# FanControllerSch.net
KiCad netlist of a schematic drawn in Altium Designer
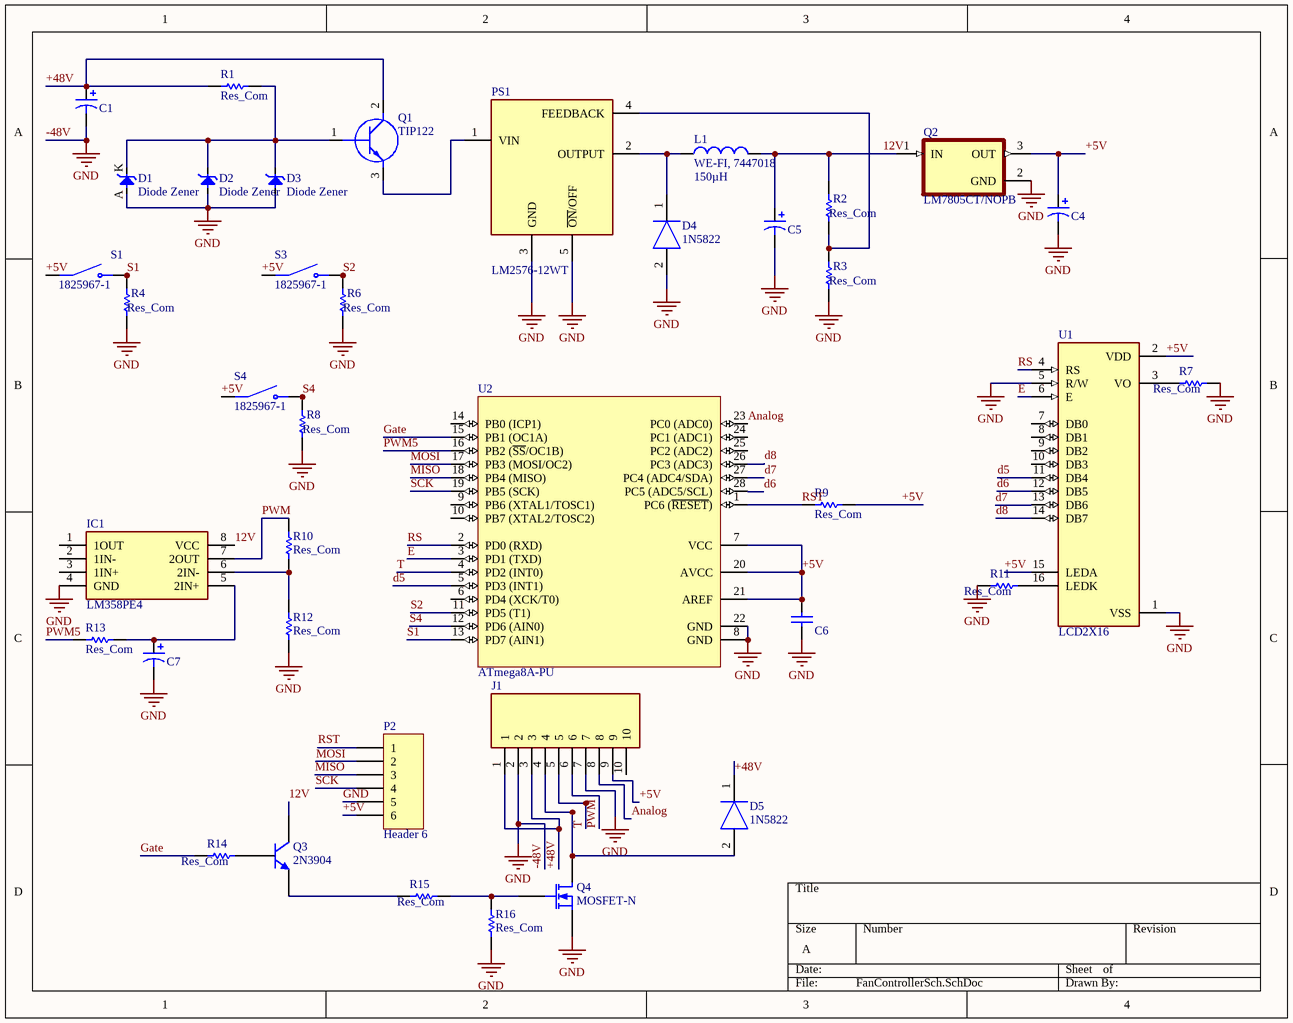
[diagram p0: FanControllerSch.SchDoc]

(export (version "E")
  (design (tool "Eeschema 10.0.6"))
  (components
    (comp (ref "C1")
      (value "100 μF")
      (footprint "Radial 12.5 x 25")
      (description "Electrolitic Capacitor, Thru-Hole")
      (fields
        (field (name "PUBLISHER") "Cynetik Group")
        (field (name "CREATED BY") "Zion Blue")
        (field (name "CONTACT") "cynetik_group@hotmail.com")
      )
      (libsource (lib "Capacitors") (part "Electrolitic Capacitor, Thru-Hole"))
    )
    (comp (ref "C4")
      (value "100 μF")
      (footprint "RADIAL 3.5x7.7")
      (description "Electrolitic Capacitor, Thru-Hole")
      (fields
        (field (name "PUBLISHER") "Cynetik Group")
        (field (name "CREATED BY") "Zion Blue")
        (field (name "CONTACT") "cynetik_group@hotmail.com")
      )
      (libsource (lib "Capacitors") (part "Electrolitic Capacitor, Thru-Hole"))
    )
    (comp (ref "C5")
      (value "100 μF")
      (footprint "RADIAL 3.5x7.7")
      (description "Electrolitic Capacitor, Thru-Hole")
      (fields
        (field (name "PUBLISHER") "Cynetik Group")
        (field (name "CREATED BY") "Zion Blue")
        (field (name "CONTACT") "cynetik_group@hotmail.com")
      )
      (libsource (lib "Capacitors") (part "Electrolitic Capacitor, Thru-Hole"))
    )
    (comp (ref "C6")
      (value "100 nF")
      (footprint "Ceramic Capacitor 2")
      (description "Ceramic Capacitor, Thru-Hole")
      (fields
        (field (name "CREATED BY") "Zion Blue")
        (field (name "PUBLISHER") "Cynetik Group")
        (field (name "CONTACT") "cynetik_group@hotmail.com")
      )
      (libsource (lib "Capacitors") (part "Ceramic Capacitor, Thru-Hole."))
    )
    (comp (ref "C7")
      (value "100 μF")
      (footprint "RADIAL 3.5x7.7")
      (description "Electrolitic Capacitor, Thru-Hole")
      (fields
        (field (name "PUBLISHER") "Cynetik Group")
        (field (name "CREATED BY") "Zion Blue")
        (field (name "CONTACT") "cynetik_group@hotmail.com")
      )
      (libsource (lib "Capacitors") (part "Electrolitic Capacitor, Thru-Hole"))
    )
    (comp (ref "D1")
      (value "Diode Zener")
      (footprint "ONSC-AXIAL_LEAD-2-59-10_P")
      (libsource (lib "") (part "Diode Zener_1"))
    )
    (comp (ref "D2")
      (value "Diode Zener")
      (footprint "ONSC-AXIAL_LEAD-2-59-10_P")
      (libsource (lib "Diodes") (part "Diode Zener"))
    )
    (comp (ref "D3")
      (value "Diode Zener")
      (footprint "ONSC-AXIAL_LEAD-2-59-10_P")
      (libsource (lib "Diodes") (part "Diode Zener"))
    )
    (comp (ref "D4")
      (value "1N5822")
      (footprint "ONSC-AXIAL_LEAD-2-59-10_P")
      (description "Diode")
      (libsource (lib "*") (part "1N5822"))
    )
    (comp (ref "D5")
      (value "1N5822")
      (footprint "ONSC-AXIAL_LEAD-2-59-10_P")
      (description "Diode")
      (libsource (lib "*") (part "1N5822"))
    )
    (comp (ref "IC1")
      (value "LM358PE4")
      (footprint "SamacSys:DIP794W53P254L959H508Q8N")
      (description "Integrated Circuit")
      (fields (field (name "MOUSER PART NUMBER") "595-LM358PE4"))
      (libsource (lib "*") (part "LM358PE4"))
    )
    (comp (ref "J1")
      (value "1-282837-0")
      (footprint "TE_1-282837-0")
      (description "TERMI-BLOK PCB MOUNT 10P")
      (fields (field (name "MF") "TE Connectivity"))
      (libsource (lib "TB-10P-5.08pitch") (part "1-282837-0"))
    )
    (comp (ref "L1")
      (value "WE-FI, 7447018")
      (footprint "TSL0709RA-102KR19-PF")
      (description "WE-FI Leaded Toroidal Line Choke, L = 150µH")
      (fields
        (field (name "PARTNO") "7447018")
        (field (name "MANUFACTURER") "Wurth Elektronik")
        (field (name "ALTIUM_VALUE") "150µH")
        (field (name "CREATED BY") "Baojun Chen")
      )
      (libsource (lib "Inductor") (part "WE-FI, 7447018"))
    )
    (comp (ref "P2")
      (value "Header 6")
      (footprint "HDR1X6")
      (description "Header, 6-Pin")
      (fields (field (name "PUBLISHER") "Altium Limited"))
      (libsource (lib "Miscellaneous Connectors") (part "Header 6"))
    )
    (comp (ref "PS1")
      (value "LM2576-12WT")
      (footprint "SamacSys:TO170P470X1016X1900-5P")
      (description "Power Supply")
      (fields (field (name "MOUSER PART NUMBER") "998-LM2576-12WT"))
      (libsource (lib "*") (part "LM2576-12WT"))
    )
    (comp (ref "Q1")
      (value "TIP122")
      (footprint "SamacSys:TO255P460X1020X2008-3P")
      (description "Transistor BJT NPN")
      (fields (field (name "MOUSER PART NUMBER") "511-TIP122"))
      (libsource (lib "*") (part "TIP122"))
    )
    (comp (ref "Q2")
      (value "LM7805CT/NOPB")
      (footprint "TO254P1054X470X2600-3")
      (description "Linear Voltage Regulator IC 1 Output 1A TO-220-3")
      (fields (field (name "MP") "LM7805CT") (field (name "MF") "ON Semiconductor"))
      (libsource (lib "LDO") (part "LM7805CT/NOPB"))
    )
    (comp (ref "Q3")
      (value "2N3904")
      (footprint "TO-92A")
      (description "NPN General Purpose Amplifier")
      (fields (field (name "PUBLISHER") "Altium Limited"))
      (libsource (lib "Miscellaneous Devices") (part "2N3904"))
    )
    (comp (ref "Q4")
      (value "MOSFET-N")
      (footprint "TO-220AB")
      (description "N-Channel MOSFET")
      (fields (field (name "PUBLISHER") "Altium Limited"))
      (libsource (lib "Miscellaneous Devices") (part "MOSFET-N"))
    )
    (comp (ref "R1")
      (value "Res_Com")
      (footprint "1K Ohm")
      (libsource (lib "Resistors_SMD_IPC-SM-782") (part "Res_Com"))
    )
    (comp (ref "R2")
      (value "Res_Com")
      (footprint "1K Ohm")
      (libsource (lib "Resistors_SMD_IPC-SM-782") (part "Res_Com"))
    )
    (comp (ref "R3")
      (value "Res_Com")
      (footprint "1K Ohm")
      (libsource (lib "Resistors_SMD_IPC-SM-782") (part "Res_Com"))
    )
    (comp (ref "R4")
      (value "Res_Com")
      (footprint "1K Ohm")
      (libsource (lib "Resistors_SMD_IPC-SM-782") (part "Res_Com"))
    )
    (comp (ref "R6")
      (value "Res_Com")
      (footprint "1K Ohm")
      (libsource (lib "Resistors_SMD_IPC-SM-782") (part "Res_Com"))
    )
    (comp (ref "R7")
      (value "Res_Com")
      (footprint "1K Ohm")
      (libsource (lib "Resistors_SMD_IPC-SM-782") (part "Res_Com"))
    )
    (comp (ref "R8")
      (value "Res_Com")
      (footprint "1K Ohm")
      (libsource (lib "Resistors_SMD_IPC-SM-782") (part "Res_Com"))
    )
    (comp (ref "R9")
      (value "Res_Com")
      (footprint "1K Ohm")
      (libsource (lib "Resistors_SMD_IPC-SM-782") (part "Res_Com"))
    )
    (comp (ref "R10")
      (value "Res_Com")
      (footprint "1K Ohm")
      (libsource (lib "Resistors_SMD_IPC-SM-782") (part "Res_Com"))
    )
    (comp (ref "R11")
      (value "Res_Com")
      (footprint "1K Ohm")
      (libsource (lib "Resistors_SMD_IPC-SM-782") (part "Res_Com"))
    )
    (comp (ref "R12")
      (value "Res_Com")
      (footprint "1K Ohm")
      (libsource (lib "Resistors_SMD_IPC-SM-782") (part "Res_Com"))
    )
    (comp (ref "R13")
      (value "Res_Com")
      (footprint "1K Ohm")
      (libsource (lib "Resistors_SMD_IPC-SM-782") (part "Res_Com"))
    )
    (comp (ref "R14")
      (value "Res_Com")
      (footprint "1K Ohm")
      (libsource (lib "Resistors_SMD_IPC-SM-782") (part "Res_Com"))
    )
    (comp (ref "R15")
      (value "Res_Com")
      (footprint "1K Ohm")
      (libsource (lib "Resistors_SMD_IPC-SM-782") (part "Res_Com"))
    )
    (comp (ref "R16")
      (value "Res_Com")
      (footprint "1K Ohm")
      (libsource (lib "Resistors_SMD_IPC-SM-782") (part "Res_Com"))
    )
    (comp (ref "S1")
      (value "1825967-1")
      (footprint "SW_1825967-1")
      (description "Switch Tactile OFF (ON) SPST Round Button PC Pins 0.05A 24VDC 1.57N Thru-Hole")
      (fields
        (field (name "MF") "TE Connectivity")
        (field (name "BUYPART") "https://www.snapeda.com/parts/1825967-1/TE%20Connectivity%20/%20DEUTSCH/view-part/398388/?ref=eda")
      )
      (libsource (lib "1825967-1") (part "1825967-1"))
    )
    (comp (ref "S3")
      (value "1825967-1")
      (footprint "SW_1825967-1")
      (description "Switch Tactile OFF (ON) SPST Round Button PC Pins 0.05A 24VDC 1.57N Thru-Hole")
      (fields
        (field (name "MF") "TE Connectivity")
        (field (name "BUYPART") "https://www.snapeda.com/parts/1825967-1/TE%20Connectivity%20/%20DEUTSCH/view-part/398388/?ref=eda")
      )
      (libsource (lib "1825967-1") (part "1825967-1"))
    )
    (comp (ref "S4")
      (value "1825967-1")
      (footprint "SW_1825967-1")
      (description "Switch Tactile OFF (ON) SPST Round Button PC Pins 0.05A 24VDC 1.57N Thru-Hole")
      (fields
        (field (name "MF") "TE Connectivity")
        (field (name "BUYPART") "https://www.snapeda.com/parts/1825967-1/TE%20Connectivity%20/%20DEUTSCH/view-part/398388/?ref=eda")
      )
      (libsource (lib "1825967-1") (part "1825967-1"))
    )
    (comp (ref "U1")
      (value "LCD2X16")
      (footprint "LCD_LCD2X16")
      (description "Display; Display: LCD 2x16 characters (blue backlight)")
      (fields (field (name "MF") "mikroElektronika"))
      (libsource (lib "LCD2X16") (part "LCD2X16"))
    )
    (comp (ref "U2") (value "ATmega8A-PU") (footprint "28P3") (libsource (lib "ICs") (part "ATmega8A-PU")))
  )
  (nets
    (net (code "1") (name "/+5V") (class "Default")
      (node (ref "C4") (pin "1") (pinfunction "1_1") (pintype "passive"))
      (node (ref "C6") (pin "2") (pinfunction "2_2") (pintype "passive"))
      (node (ref "J1") (pin "9") (pinfunction "9_9") (pintype "passive"))
      (node (ref "P2") (pin "6") (pinfunction "6_6") (pintype "passive"))
      (node (ref "Q2") (pin "3") (pinfunction "OUT_3") (pintype "output"))
      (node (ref "R9") (pin "2") (pinfunction "2_2") (pintype "passive"))
      (node (ref "S1") (pin "1") (pinfunction "COM_1") (pintype "passive"))
      (node (ref "S1") (pin "2") (pinfunction "COM_2") (pintype "passive"))
      (node (ref "S3") (pin "1") (pinfunction "COM_1") (pintype "passive"))
      (node (ref "S3") (pin "2") (pinfunction "COM_2") (pintype "passive"))
      (node (ref "S4") (pin "1") (pinfunction "COM_1") (pintype "passive"))
      (node (ref "S4") (pin "2") (pinfunction "COM_2") (pintype "passive"))
      (node (ref "U1") (pin "15") (pinfunction "LEDA_15") (pintype "passive"))
      (node (ref "U1") (pin "2") (pinfunction "VDD_2") (pintype "power_in"))
      (node (ref "U2") (pin "20") (pinfunction "AVCC_20") (pintype "power_in"))
      (node (ref "U2") (pin "21") (pinfunction "AREF_21") (pintype "passive"))
      (node (ref "U2") (pin "7") (pinfunction "VCC_7") (pintype "power_in"))
    )
    (net (code "2") (name "/+48V") (class "Default")
      (node (ref "C1") (pin "1") (pinfunction "1_1") (pintype "passive"))
      (node (ref "D5") (pin "1") (pinfunction "K_1") (pintype "passive"))
      (node (ref "J1") (pin "1") (pinfunction "1_1") (pintype "passive"))
      (node (ref "J1") (pin "3") (pinfunction "3_3") (pintype "passive"))
      (node (ref "Q1") (pin "2") (pinfunction "C_2") (pintype "passive"))
      (node (ref "R1") (pin "2") (pinfunction "2_2") (pintype "passive"))
    )
    (net (code "3") (name "/12V") (class "Default")
      (node (ref "C5") (pin "1") (pinfunction "1_1") (pintype "passive"))
      (node (ref "IC1") (pin "8") (pinfunction "VCC_8") (pintype "passive"))
      (node (ref "L1") (pin "2") (pinfunction "2_2") (pintype "passive"))
      (node (ref "Q2") (pin "1") (pinfunction "IN_1") (pintype "input"))
      (node (ref "Q3") (pin "3") (pinfunction "C_3") (pintype "passive"))
      (node (ref "R2") (pin "2") (pinfunction "2_2") (pintype "passive"))
    )
    (net (code "4") (name "/Analog") (class "Default")
      (node (ref "J1") (pin "8") (pinfunction "8_8") (pintype "passive"))
      (node (ref "U2") (pin "23") (pinfunction "PC0_(ADC0)_23") (pintype "bidirectional"))
    )
    (net (code "5") (name "/E") (class "Default")
      (node (ref "U1") (pin "6") (pinfunction "E_6") (pintype "input"))
      (node (ref "U2") (pin "3") (pinfunction "PD1_(TXD)_3") (pintype "bidirectional"))
    )
    (net (code "6") (name "/Gate") (class "Default")
      (node (ref "R14") (pin "2") (pinfunction "2_2") (pintype "passive"))
      (node (ref "U2") (pin "15") (pinfunction "PB1_(OC1A)_15") (pintype "bidirectional"))
    )
    (net (code "7") (name "/MISO") (class "Default")
      (node (ref "P2") (pin "3") (pinfunction "3_3") (pintype "passive"))
      (node (ref "U2") (pin "18") (pinfunction "PB4_(MISO)_18") (pintype "bidirectional"))
    )
    (net (code "8") (name "/MOSI") (class "Default")
      (node (ref "P2") (pin "2") (pinfunction "2_2") (pintype "passive"))
      (node (ref "U2") (pin "17") (pinfunction "PB3_(MOSI/OC2)_17") (pintype "bidirectional"))
    )
    (net (code "9") (name "/PWM") (class "Default")
      (node (ref "IC1") (pin "7") (pinfunction "2OUT_7") (pintype "passive"))
      (node (ref "J1") (pin "6") (pinfunction "6_6") (pintype "passive"))
      (node (ref "R10") (pin "1") (pinfunction "1_1") (pintype "passive"))
    )
    (net (code "10") (name "/PWM5") (class "Default")
      (node (ref "R13") (pin "2") (pinfunction "2_2") (pintype "passive"))
      (node (ref "U2") (pin "16") (pinfunction "PB2_(~{SS}/OC1B)_16") (pintype "bidirectional"))
    )
    (net (code "11") (name "/RS") (class "Default")
      (node (ref "U1") (pin "4") (pinfunction "RS_4") (pintype "input"))
      (node (ref "U2") (pin "2") (pinfunction "PD0_(RXD)_2") (pintype "bidirectional"))
    )
    (net (code "12") (name "/RST") (class "Default")
      (node (ref "P2") (pin "1") (pinfunction "1_1") (pintype "passive"))
      (node (ref "R9") (pin "1") (pinfunction "1_1") (pintype "passive"))
      (node (ref "U2") (pin "1") (pinfunction "PC6_(~{RESET})_1") (pintype "bidirectional"))
    )
    (net (code "13") (name "/S1") (class "Default")
      (node (ref "R4") (pin "2") (pinfunction "2_2") (pintype "passive"))
      (node (ref "S1") (pin "3") (pinfunction "NO_3") (pintype "passive"))
      (node (ref "S1") (pin "4") (pinfunction "NO_4") (pintype "passive"))
      (node (ref "U2") (pin "13") (pinfunction "PD7_(AIN1)_13") (pintype "bidirectional"))
    )
    (net (code "14") (name "/S2") (class "Default")
      (node (ref "R6") (pin "2") (pinfunction "2_2") (pintype "passive"))
      (node (ref "S3") (pin "3") (pinfunction "NO_3") (pintype "passive"))
      (node (ref "S3") (pin "4") (pinfunction "NO_4") (pintype "passive"))
      (node (ref "U2") (pin "11") (pinfunction "PD5_(T1)_11") (pintype "bidirectional"))
    )
    (net (code "15") (name "/S4") (class "Default")
      (node (ref "R8") (pin "2") (pinfunction "2_2") (pintype "passive"))
      (node (ref "S4") (pin "3") (pinfunction "NO_3") (pintype "passive"))
      (node (ref "S4") (pin "4") (pinfunction "NO_4") (pintype "passive"))
      (node (ref "U2") (pin "12") (pinfunction "PD6_(AIN0)_12") (pintype "bidirectional"))
    )
    (net (code "16") (name "/SCK") (class "Default")
      (node (ref "P2") (pin "4") (pinfunction "4_4") (pintype "passive"))
      (node (ref "U2") (pin "19") (pinfunction "PB5_(SCK)_19") (pintype "bidirectional"))
    )
    (net (code "17") (name "/T") (class "Default")
      (node (ref "J1") (pin "5") (pinfunction "5_5") (pintype "passive"))
      (node (ref "U2") (pin "4") (pinfunction "PD2_(INT0)_4") (pintype "bidirectional"))
    )
    (net (code "18") (name "/d5") (class "Default")
      (node (ref "U1") (pin "11") (pinfunction "DB4_11") (pintype "bidirectional"))
      (node (ref "U2") (pin "5") (pinfunction "PD3_(INT1)_5") (pintype "bidirectional"))
    )
    (net (code "19") (name "/d6") (class "Default")
      (node (ref "U1") (pin "12") (pinfunction "DB5_12") (pintype "bidirectional"))
      (node (ref "U2") (pin "28") (pinfunction "PC5_(ADC5/SCL)_28") (pintype "bidirectional"))
    )
    (net (code "20") (name "/d7") (class "Default")
      (node (ref "U1") (pin "13") (pinfunction "DB6_13") (pintype "bidirectional"))
      (node (ref "U2") (pin "27") (pinfunction "PC4_(ADC4/SDA)_27") (pintype "bidirectional"))
    )
    (net (code "21") (name "/d8") (class "Default")
      (node (ref "U1") (pin "14") (pinfunction "DB7_14") (pintype "bidirectional"))
      (node (ref "U2") (pin "26") (pinfunction "PC3_(ADC3)_26") (pintype "bidirectional"))
    )
    (net (code "22") (name "GND") (class "Default")
      (node (ref "C1") (pin "2") (pinfunction "2_2") (pintype "passive"))
      (node (ref "C4") (pin "2") (pinfunction "2_2") (pintype "passive"))
      (node (ref "C5") (pin "2") (pinfunction "2_2") (pintype "passive"))
      (node (ref "C6") (pin "1") (pinfunction "1_1") (pintype "passive"))
      (node (ref "C7") (pin "2") (pinfunction "2_2") (pintype "passive"))
      (node (ref "D1") (pin "A") (pinfunction "A_A") (pintype "passive"))
      (node (ref "D2") (pin "A") (pinfunction "A_A") (pintype "passive"))
      (node (ref "D3") (pin "A") (pinfunction "A_A") (pintype "passive"))
      (node (ref "D4") (pin "2") (pinfunction "A_2") (pintype "passive"))
      (node (ref "IC1") (pin "4") (pinfunction "GND_4") (pintype "passive"))
      (node (ref "J1") (pin "2") (pinfunction "2_2") (pintype "passive"))
      (node (ref "J1") (pin "7") (pinfunction "7_7") (pintype "passive"))
      (node (ref "P2") (pin "5") (pinfunction "5_5") (pintype "passive"))
      (node (ref "PS1") (pin "3") (pinfunction "GND_3") (pintype "passive"))
      (node (ref "PS1") (pin "5") (pinfunction "~{ON}/OFF_5") (pintype "passive"))
      (node (ref "Q2") (pin "2") (pinfunction "GND_2") (pintype "power_in"))
      (node (ref "Q4") (pin "3") (pinfunction "S_3") (pintype "passive"))
      (node (ref "R11") (pin "2") (pinfunction "2_2") (pintype "passive"))
      (node (ref "R12") (pin "2") (pinfunction "2_2") (pintype "passive"))
      (node (ref "R16") (pin "2") (pinfunction "2_2") (pintype "passive"))
      (node (ref "R3") (pin "1") (pinfunction "1_1") (pintype "passive"))
      (node (ref "R4") (pin "1") (pinfunction "1_1") (pintype "passive"))
      (node (ref "R6") (pin "1") (pinfunction "1_1") (pintype "passive"))
      (node (ref "R7") (pin "1") (pinfunction "1_1") (pintype "passive"))
      (node (ref "R8") (pin "1") (pinfunction "1_1") (pintype "passive"))
      (node (ref "U1") (pin "1") (pinfunction "VSS_1") (pintype "power_in"))
      (node (ref "U1") (pin "5") (pinfunction "R/W_5") (pintype "input"))
      (node (ref "U2") (pin "22") (pinfunction "GND_22") (pintype "power_in"))
      (node (ref "U2") (pin "8") (pinfunction "GND_8") (pintype "power_in"))
    )
    (net (code "23") (name "Net-(D4-K)") (class "Default")
      (node (ref "D4") (pin "1") (pinfunction "K_1") (pintype "passive"))
      (node (ref "L1") (pin "1") (pinfunction "1_1") (pintype "passive"))
      (node (ref "PS1") (pin "2") (pinfunction "OUTPUT_2") (pintype "passive"))
    )
    (net (code "24") (name "Net-(D5-A)") (class "Default")
      (node (ref "D5") (pin "2") (pinfunction "A_2") (pintype "passive"))
      (node (ref "J1") (pin "4") (pinfunction "4_4") (pintype "passive"))
      (node (ref "Q4") (pin "1") (pinfunction "D_1") (pintype "passive"))
    )
    (net (code "25") (name "Net-(IC1-2IN+)") (class "Default")
      (node (ref "C7") (pin "1") (pinfunction "1_1") (pintype "passive"))
      (node (ref "IC1") (pin "5") (pinfunction "2IN+_5") (pintype "passive"))
      (node (ref "R13") (pin "1") (pinfunction "1_1") (pintype "passive"))
    )
    (net (code "26") (name "Net-(IC1-2IN-)") (class "Default")
      (node (ref "IC1") (pin "6") (pinfunction "2IN-_6") (pintype "passive"))
      (node (ref "R10") (pin "2") (pinfunction "2_2") (pintype "passive"))
      (node (ref "R12") (pin "1") (pinfunction "1_1") (pintype "passive"))
    )
    (net (code "27") (name "Net-(PS1-FEEDBACK)") (class "Default")
      (node (ref "PS1") (pin "4") (pinfunction "FEEDBACK_4") (pintype "passive"))
      (node (ref "R2") (pin "1") (pinfunction "1_1") (pintype "passive"))
      (node (ref "R3") (pin "2") (pinfunction "2_2") (pintype "passive"))
    )
    (net (code "28") (name "Net-(PS1-VIN)") (class "Default")
      (node (ref "PS1") (pin "1") (pinfunction "VIN_1") (pintype "passive"))
      (node (ref "Q1") (pin "3") (pinfunction "E_3") (pintype "passive"))
    )
    (net (code "29") (name "Net-(Q1-B)") (class "Default")
      (node (ref "D1") (pin "K") (pinfunction "K_K") (pintype "passive"))
      (node (ref "D2") (pin "K") (pinfunction "K_K") (pintype "passive"))
      (node (ref "D3") (pin "K") (pinfunction "K_K") (pintype "passive"))
      (node (ref "Q1") (pin "1") (pinfunction "B_1") (pintype "passive"))
      (node (ref "R1") (pin "1") (pinfunction "1_1") (pintype "passive"))
    )
    (net (code "30") (name "Net-(Q3-B)") (class "Default")
      (node (ref "Q3") (pin "2") (pinfunction "B_2") (pintype "passive"))
      (node (ref "R14") (pin "1") (pinfunction "1_1") (pintype "passive"))
    )
    (net (code "31") (name "Net-(Q3-E)") (class "Default")
      (node (ref "Q3") (pin "1") (pinfunction "E_1") (pintype "passive"))
      (node (ref "R15") (pin "2") (pinfunction "2_2") (pintype "passive"))
    )
    (net (code "32") (name "Net-(Q4-G)") (class "Default")
      (node (ref "Q4") (pin "2") (pinfunction "G_2") (pintype "passive"))
      (node (ref "R15") (pin "1") (pinfunction "1_1") (pintype "passive"))
      (node (ref "R16") (pin "1") (pinfunction "1_1") (pintype "passive"))
    )
    (net (code "33") (name "Net-(U1-LEDK)") (class "Default")
      (node (ref "R11") (pin "1") (pinfunction "1_1") (pintype "passive"))
      (node (ref "U1") (pin "16") (pinfunction "LEDK_16") (pintype "passive"))
    )
    (net (code "34") (name "Net-(U1-VO)") (class "Default")
      (node (ref "R7") (pin "2") (pinfunction "2_2") (pintype "passive"))
      (node (ref "U1") (pin "3") (pinfunction "VO_3") (pintype "passive"))
    )
    (net (code "35") (name "unconnected-(IC1-1IN+-Pad3)") (class "Default")
      (node (ref "IC1") (pin "3") (pinfunction "1IN+_3") (pintype "passive"))
    )
    (net (code "36") (name "unconnected-(IC1-1IN--Pad2)") (class "Default")
      (node (ref "IC1") (pin "2") (pinfunction "1IN-_2") (pintype "passive"))
    )
    (net (code "37") (name "unconnected-(IC1-1OUT-Pad1)") (class "Default")
      (node (ref "IC1") (pin "1") (pinfunction "1OUT_1") (pintype "passive"))
    )
    (net (code "38") (name "unconnected-(J1-Pad10)") (class "Default")
      (node (ref "J1") (pin "10") (pinfunction "10_10") (pintype "passive"))
    )
    (net (code "39") (name "unconnected-(U1-DB0-Pad7)") (class "Default")
      (node (ref "U1") (pin "7") (pinfunction "DB0_7") (pintype "bidirectional"))
    )
    (net (code "40") (name "unconnected-(U1-DB1-Pad8)") (class "Default")
      (node (ref "U1") (pin "8") (pinfunction "DB1_8") (pintype "bidirectional"))
    )
    (net (code "41") (name "unconnected-(U1-DB2-Pad9)") (class "Default")
      (node (ref "U1") (pin "9") (pinfunction "DB2_9") (pintype "bidirectional"))
    )
    (net (code "42") (name "unconnected-(U1-DB3-Pad10)") (class "Default")
      (node (ref "U1") (pin "10") (pinfunction "DB3_10") (pintype "bidirectional"))
    )
    (net (code "43") (name "unconnected-(U2-PB0_(ICP1)-Pad14)") (class "Default")
      (node (ref "U2") (pin "14") (pinfunction "PB0_(ICP1)_14") (pintype "bidirectional"))
    )
    (net (code "44") (name "unconnected-(U2-PB6_(XTAL1{slash}TOSC1)-Pad9)") (class "Default")
      (node (ref "U2") (pin "9") (pinfunction "PB6_(XTAL1/TOSC1)_9") (pintype "bidirectional"))
    )
    (net (code "45") (name "unconnected-(U2-PB7_(XTAL2{slash}TOSC2)-Pad10)") (class "Default")
      (node (ref "U2") (pin "10") (pinfunction "PB7_(XTAL2/TOSC2)_10") (pintype "bidirectional"))
    )
    (net (code "46") (name "unconnected-(U2-PC1_(ADC1)-Pad24)") (class "Default")
      (node (ref "U2") (pin "24") (pinfunction "PC1_(ADC1)_24") (pintype "bidirectional"))
    )
    (net (code "47") (name "unconnected-(U2-PC2_(ADC2)-Pad25)") (class "Default")
      (node (ref "U2") (pin "25") (pinfunction "PC2_(ADC2)_25") (pintype "bidirectional"))
    )
    (net (code "48") (name "unconnected-(U2-PD4_(XCK{slash}T0)-Pad6)") (class "Default")
      (node (ref "U2") (pin "6") (pinfunction "PD4_(XCK/T0)_6") (pintype "bidirectional"))
    )
  )
)
